# IRBumper_AB.net
KiCad netlist of a schematic drawn in EAGLE
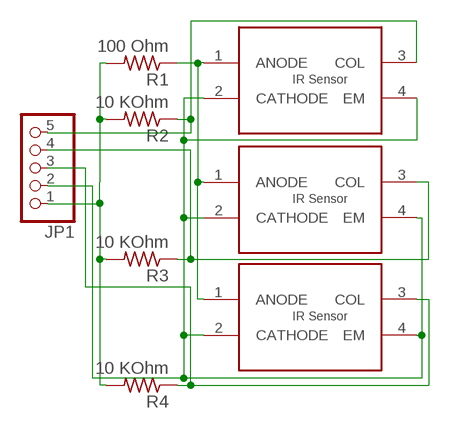
[diagram p0: schematic, sheet 1]

(export (version "E")
  (design (tool "Eeschema 10.0.6"))
  (components
    (comp (ref "JP1")
      (value "PINHD-1X5")
      (footprint "eagle-import:1X05")
      (libsource (lib "eagle-import") (part "PINHD-1X5"))
    )
    (comp (ref "R1")
      (value "100 Ohm")
      (footprint "eagle-import:M0805")
      (libsource (lib "eagle-import") (part "R-US_M0805"))
    )
    (comp (ref "R2")
      (value "10 KOhm")
      (footprint "eagle-import:M0805")
      (libsource (lib "eagle-import") (part "R-US_M0805"))
    )
    (comp (ref "R3")
      (value "10 KOhm")
      (footprint "eagle-import:M0805")
      (libsource (lib "eagle-import") (part "R-US_M0805"))
    )
    (comp (ref "R4")
      (value "10 KOhm")
      (footprint "eagle-import:M0805")
      (libsource (lib "eagle-import") (part "R-US_M0805"))
    )
    (comp (ref "U$1")
      (value "QRE1113GR")
      (footprint "eagle-import:4-SMD")
      (libsource (lib "eagle-import") (part "QRE1113GR"))
    )
    (comp (ref "U$2")
      (value "QRE1113GR")
      (footprint "eagle-import:4-SMD")
      (libsource (lib "eagle-import") (part "QRE1113GR"))
    )
    (comp (ref "U$3")
      (value "QRE1113GR")
      (footprint "eagle-import:4-SMD")
      (libsource (lib "eagle-import") (part "QRE1113GR"))
    )
  )
  (nets
    (net (code "1") (name "Net-(JP1-Pad1)") (class "Default")
      (node (ref "JP1") (pin "1") (pinfunction "1_1") (pintype "passive"))
      (node (ref "R1") (pin "2") (pinfunction "2_2") (pintype "passive"))
      (node (ref "R2") (pin "2") (pinfunction "2_2") (pintype "passive"))
      (node (ref "R3") (pin "2") (pinfunction "2_2") (pintype "passive"))
      (node (ref "R4") (pin "2") (pinfunction "2_2") (pintype "passive"))
    )
    (net (code "2") (name "Net-(U$1-ANODE)") (class "Default")
      (node (ref "R1") (pin "1") (pinfunction "1_1") (pintype "passive"))
      (node (ref "U$1") (pin "1") (pinfunction "ANODE_1") (pintype "bidirectional"))
      (node (ref "U$2") (pin "1") (pinfunction "ANODE_1") (pintype "bidirectional"))
      (node (ref "U$3") (pin "1") (pinfunction "ANODE_1") (pintype "bidirectional"))
    )
    (net (code "3") (name "Net-(U$1-CATHODE)") (class "Default")
      (node (ref "JP1") (pin "2") (pinfunction "2_2") (pintype "passive"))
      (node (ref "U$1") (pin "2") (pinfunction "CATHODE_2") (pintype "bidirectional"))
      (node (ref "U$1") (pin "4") (pinfunction "EM_4") (pintype "bidirectional"))
      (node (ref "U$2") (pin "2") (pinfunction "CATHODE_2") (pintype "bidirectional"))
      (node (ref "U$2") (pin "4") (pinfunction "EM_4") (pintype "bidirectional"))
      (node (ref "U$3") (pin "2") (pinfunction "CATHODE_2") (pintype "bidirectional"))
      (node (ref "U$3") (pin "4") (pinfunction "EM_4") (pintype "bidirectional"))
    )
    (net (code "4") (name "Net-(U$1-COL)") (class "Default")
      (node (ref "JP1") (pin "4") (pinfunction "4_4") (pintype "passive"))
      (node (ref "R3") (pin "1") (pinfunction "1_1") (pintype "passive"))
      (node (ref "U$1") (pin "3") (pinfunction "COL_3") (pintype "bidirectional"))
    )
    (net (code "5") (name "Net-(U$2-COL)") (class "Default")
      (node (ref "JP1") (pin "5") (pinfunction "5_5") (pintype "passive"))
      (node (ref "R2") (pin "1") (pinfunction "1_1") (pintype "passive"))
      (node (ref "U$2") (pin "3") (pinfunction "COL_3") (pintype "bidirectional"))
    )
    (net (code "6") (name "Net-(U$3-COL)") (class "Default")
      (node (ref "JP1") (pin "3") (pinfunction "3_3") (pintype "passive"))
      (node (ref "R4") (pin "1") (pinfunction "1_1") (pintype "passive"))
      (node (ref "U$3") (pin "3") (pinfunction "COL_3") (pintype "bidirectional"))
    )
  )
)
